# ANALOG_DATA.net
KiCad netlist of a schematic drawn in Altium Designer
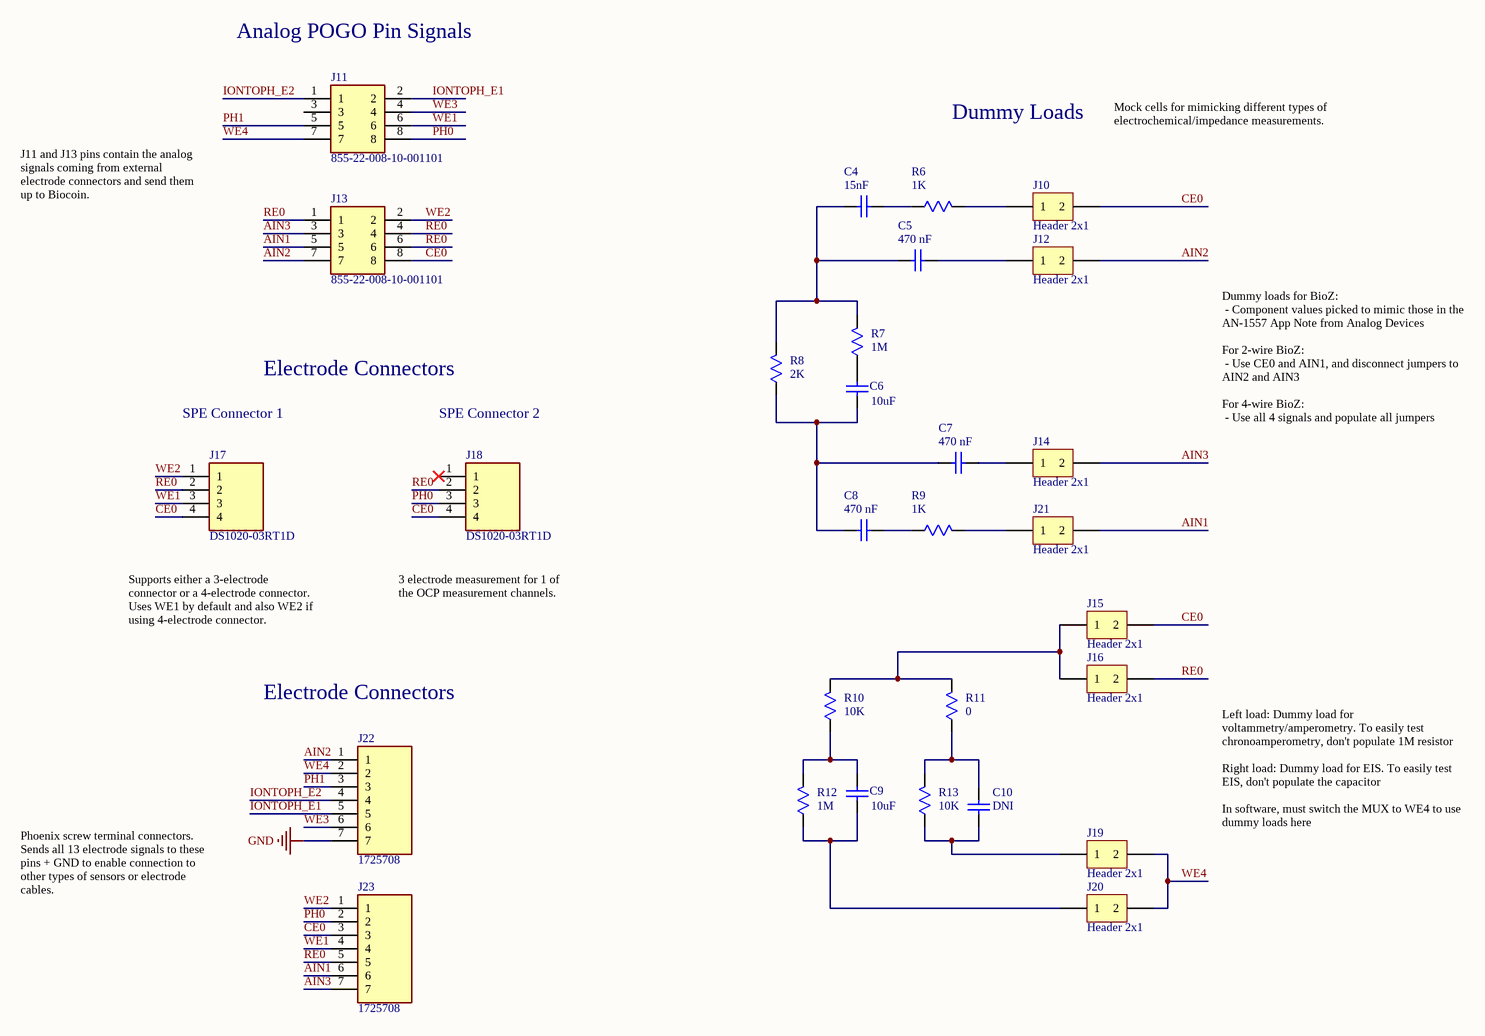
[diagram p0: ANALOG_DATA.SchDoc]

(export (version "E")
  (design (tool "Eeschema 10.0.6"))
  (components
    (comp (ref "C4")
      (value "15nF")
      (footprint "0805-CAP")
      (description "Multilayer Chip Capacitor")
      (fields (field (name "Comment") "CAP") (field (name "DESIGNER") "OMIGA"))
      (libsource (lib "Schlib") (part "CAP SMD"))
    )
    (comp (ref "C5")
      (value "470 nF")
      (footprint "0805-CAP")
      (description "Multilayer Chip Capacitor")
      (fields (field (name "Comment") "CAP") (field (name "DESIGNER") "OMIGA"))
      (libsource (lib "Schlib") (part "CAP SMD"))
    )
    (comp (ref "C6")
      (value "10uF")
      (footprint "0805-CAP")
      (description "Multilayer Chip Capacitor")
      (fields (field (name "Comment") "CAP") (field (name "DESIGNER") "OMIGA"))
      (libsource (lib "Schlib") (part "CAP SMD"))
    )
    (comp (ref "C7")
      (value "470 nF")
      (footprint "0805-CAP")
      (description "Multilayer Chip Capacitor")
      (fields (field (name "Comment") "CAP") (field (name "DESIGNER") "OMIGA"))
      (libsource (lib "Schlib") (part "CAP SMD"))
    )
    (comp (ref "C8")
      (value "470 nF")
      (footprint "0805-CAP")
      (description "Multilayer Chip Capacitor")
      (fields (field (name "Comment") "CAP") (field (name "DESIGNER") "OMIGA"))
      (libsource (lib "Schlib") (part "CAP SMD"))
    )
    (comp (ref "C9")
      (value "10uF")
      (footprint "0805-CAP")
      (description "Multilayer Chip Capacitor")
      (fields (field (name "Comment") "CAP") (field (name "DESIGNER") "OMIGA"))
      (libsource (lib "Schlib") (part "CAP SMD"))
    )
    (comp (ref "C10")
      (value "DNI")
      (footprint "0805-CAP")
      (description "Multilayer Chip Capacitor")
      (fields (field (name "Comment") "CAP") (field (name "DESIGNER") "OMIGA"))
      (libsource (lib "Schlib") (part "CAP SMD"))
    )
    (comp (ref "J10")
      (value "Header 2x1")
      (footprint "Header 1x2")
      (description "Pin Header 2x1")
      (fields (field (name "DESIGNER") "OMIGA"))
      (libsource (lib "Schlib") (part "Header 2x1"))
    )
    (comp (ref "J11")
      (value "855-22-008-10-001101")
      (footprint "8552200810001101")
      (libsource (lib "Schlib") (part "8 pin Pogo Pin Male Header"))
    )
    (comp (ref "J12")
      (value "Header 2x1")
      (footprint "Header 1x2")
      (description "Pin Header 2x1")
      (fields (field (name "DESIGNER") "OMIGA"))
      (libsource (lib "Schlib") (part "Header 2x1"))
    )
    (comp (ref "J13")
      (value "855-22-008-10-001101")
      (footprint "8552200810001101")
      (libsource (lib "Schlib") (part "8 pin Pogo Pin Male Header"))
    )
    (comp (ref "J14")
      (value "Header 2x1")
      (footprint "Header 1x2")
      (description "Pin Header 2x1")
      (fields (field (name "DESIGNER") "OMIGA"))
      (libsource (lib "Schlib") (part "Header 2x1"))
    )
    (comp (ref "J15")
      (value "Header 2x1")
      (footprint "Header 1x2")
      (description "Pin Header 2x1")
      (fields (field (name "DESIGNER") "OMIGA"))
      (libsource (lib "Schlib") (part "Header 2x1"))
    )
    (comp (ref "J16")
      (value "Header 2x1")
      (footprint "Header 1x2")
      (description "Pin Header 2x1")
      (fields (field (name "DESIGNER") "OMIGA"))
      (libsource (lib "Schlib") (part "Header 2x1"))
    )
    (comp (ref "J17")
      (value "DS1020-03RT1D")
      (footprint "55203144-2")
      (description "3 pin right angle SPE connector. Can also use the 5-520315-3-ND")
      (libsource (lib "Schlib") (part "SPE Connector 3 pin"))
    )
    (comp (ref "J18")
      (value "DS1020-03RT1D")
      (footprint "55203144-2")
      (description "3 pin right angle SPE connector. Can also use the 5-520315-3-ND")
      (libsource (lib "Schlib") (part "SPE Connector 3 pin"))
    )
    (comp (ref "J19")
      (value "Header 2x1")
      (footprint "Header 1x2")
      (description "Pin Header 2x1")
      (fields (field (name "DESIGNER") "OMIGA"))
      (libsource (lib "Schlib") (part "Header 2x1"))
    )
    (comp (ref "J20")
      (value "Header 2x1")
      (footprint "Header 1x2")
      (description "Pin Header 2x1")
      (fields (field (name "DESIGNER") "OMIGA"))
      (libsource (lib "Schlib") (part "Header 2x1"))
    )
    (comp (ref "J21")
      (value "Header 2x1")
      (footprint "Header 1x2")
      (description "Pin Header 2x1")
      (fields (field (name "DESIGNER") "OMIGA"))
      (libsource (lib "Schlib") (part "Header 2x1"))
    )
    (comp (ref "J22")
      (value "1725708")
      (footprint "1725708")
      (description "Connector")
      (libsource (lib "Schlib") (part "1725708"))
    )
    (comp (ref "J23")
      (value "1725708")
      (footprint "1725708")
      (description "Connector")
      (libsource (lib "Schlib") (part "1725708"))
    )
    (comp (ref "R6")
      (value "1K")
      (footprint "0805-RES")
      (description "Surface Mount Resistor")
      (fields (field (name "Comment") "RES") (field (name "DESIGNER") "OMIGA"))
      (libsource (lib "Schlib") (part "RES SMD"))
    )
    (comp (ref "R7")
      (value "1M")
      (footprint "0805-RES")
      (description "Surface Mount Resistor")
      (fields (field (name "Comment") "RES") (field (name "DESIGNER") "OMIGA"))
      (libsource (lib "Schlib") (part "RES SMD"))
    )
    (comp (ref "R8")
      (value "2K")
      (footprint "0805-RES")
      (description "Surface Mount Resistor")
      (fields (field (name "Comment") "RES") (field (name "DESIGNER") "OMIGA"))
      (libsource (lib "Schlib") (part "RES SMD"))
    )
    (comp (ref "R9")
      (value "1K")
      (footprint "0805-RES")
      (description "Surface Mount Resistor")
      (fields (field (name "Comment") "RES") (field (name "DESIGNER") "OMIGA"))
      (libsource (lib "Schlib") (part "RES SMD"))
    )
    (comp (ref "R10")
      (value "10K")
      (footprint "0805-RES")
      (description "Surface Mount Resistor")
      (fields (field (name "Comment") "RES") (field (name "DESIGNER") "OMIGA"))
      (libsource (lib "Schlib") (part "RES SMD"))
    )
    (comp (ref "R11")
      (value "0")
      (footprint "0805-RES")
      (description "Surface Mount Resistor")
      (fields (field (name "Comment") "RES") (field (name "DESIGNER") "OMIGA"))
      (libsource (lib "Schlib") (part "RES SMD"))
    )
    (comp (ref "R12")
      (value "1M")
      (footprint "0805-RES")
      (description "Surface Mount Resistor")
      (fields (field (name "Comment") "RES") (field (name "DESIGNER") "OMIGA"))
      (libsource (lib "Schlib") (part "RES SMD"))
    )
    (comp (ref "R13")
      (value "10K")
      (footprint "0805-RES")
      (description "Surface Mount Resistor")
      (fields (field (name "Comment") "RES") (field (name "DESIGNER") "OMIGA"))
      (libsource (lib "Schlib") (part "RES SMD"))
    )
  )
  (nets
    (net (code "1") (name "/AIN1") (class "Default")
      (node (ref "J13") (pin "5") (pinfunction "5_5") (pintype "passive"))
      (node (ref "J21") (pin "2") (pinfunction "2_2") (pintype "passive"))
      (node (ref "J23") (pin "6") (pinfunction "6_6") (pintype "passive"))
    )
    (net (code "2") (name "/AIN2") (class "Default")
      (node (ref "J12") (pin "2") (pinfunction "2_2") (pintype "passive"))
      (node (ref "J13") (pin "7") (pinfunction "7_7") (pintype "passive"))
      (node (ref "J22") (pin "1") (pinfunction "1_1") (pintype "passive"))
    )
    (net (code "3") (name "/AIN3") (class "Default")
      (node (ref "J13") (pin "3") (pinfunction "3_3") (pintype "passive"))
      (node (ref "J14") (pin "2") (pinfunction "2_2") (pintype "passive"))
      (node (ref "J23") (pin "7") (pinfunction "7_7") (pintype "passive"))
    )
    (net (code "4") (name "/CE0") (class "Default")
      (node (ref "J10") (pin "2") (pinfunction "2_2") (pintype "passive"))
      (node (ref "J13") (pin "8") (pinfunction "8_8") (pintype "passive"))
      (node (ref "J15") (pin "2") (pinfunction "2_2") (pintype "passive"))
      (node (ref "J17") (pin "4") (pinfunction "4_4") (pintype "passive"))
      (node (ref "J18") (pin "4") (pinfunction "4_4") (pintype "passive"))
      (node (ref "J23") (pin "3") (pinfunction "3_3") (pintype "passive"))
    )
    (net (code "5") (name "/IONTOPH_E1") (class "Default")
      (node (ref "J11") (pin "2") (pinfunction "2_2") (pintype "passive"))
      (node (ref "J22") (pin "5") (pinfunction "5_5") (pintype "passive"))
    )
    (net (code "6") (name "/IONTOPH_E2") (class "Default")
      (node (ref "J11") (pin "1") (pinfunction "1_1") (pintype "passive"))
      (node (ref "J22") (pin "4") (pinfunction "4_4") (pintype "passive"))
    )
    (net (code "7") (name "/PH0") (class "Default")
      (node (ref "J11") (pin "8") (pinfunction "8_8") (pintype "passive"))
      (node (ref "J18") (pin "3") (pinfunction "3_3") (pintype "passive"))
      (node (ref "J23") (pin "2") (pinfunction "2_2") (pintype "passive"))
    )
    (net (code "8") (name "/PH1") (class "Default")
      (node (ref "J11") (pin "5") (pinfunction "5_5") (pintype "passive"))
      (node (ref "J22") (pin "3") (pinfunction "3_3") (pintype "passive"))
    )
    (net (code "9") (name "/RE0") (class "Default")
      (node (ref "J13") (pin "1") (pinfunction "1_1") (pintype "passive"))
      (node (ref "J13") (pin "4") (pinfunction "4_4") (pintype "passive"))
      (node (ref "J13") (pin "6") (pinfunction "6_6") (pintype "passive"))
      (node (ref "J16") (pin "2") (pinfunction "2_2") (pintype "passive"))
      (node (ref "J17") (pin "2") (pinfunction "2_2") (pintype "passive"))
      (node (ref "J18") (pin "2") (pinfunction "2_2") (pintype "passive"))
      (node (ref "J23") (pin "5") (pinfunction "5_5") (pintype "passive"))
    )
    (net (code "10") (name "/WE1") (class "Default")
      (node (ref "J11") (pin "6") (pinfunction "6_6") (pintype "passive"))
      (node (ref "J17") (pin "3") (pinfunction "3_3") (pintype "passive"))
      (node (ref "J23") (pin "4") (pinfunction "4_4") (pintype "passive"))
    )
    (net (code "11") (name "/WE2") (class "Default")
      (node (ref "J13") (pin "2") (pinfunction "2_2") (pintype "passive"))
      (node (ref "J17") (pin "1") (pinfunction "1_1") (pintype "passive"))
      (node (ref "J23") (pin "1") (pinfunction "1_1") (pintype "passive"))
    )
    (net (code "12") (name "/WE3") (class "Default")
      (node (ref "J11") (pin "4") (pinfunction "4_4") (pintype "passive"))
      (node (ref "J22") (pin "6") (pinfunction "6_6") (pintype "passive"))
    )
    (net (code "13") (name "/WE4") (class "Default")
      (node (ref "J11") (pin "7") (pinfunction "7_7") (pintype "passive"))
      (node (ref "J19") (pin "2") (pinfunction "2_2") (pintype "passive"))
      (node (ref "J20") (pin "2") (pinfunction "2_2") (pintype "passive"))
      (node (ref "J22") (pin "2") (pinfunction "2_2") (pintype "passive"))
    )
    (net (code "14") (name "GND") (class "Default")
      (node (ref "J22") (pin "7") (pinfunction "7_7") (pintype "passive"))
    )
    (net (code "15") (name "Net-(C4-Pad1)") (class "Default")
      (node (ref "C4") (pin "1") (pinfunction "1_1") (pintype "passive"))
      (node (ref "C5") (pin "1") (pinfunction "1_1") (pintype "passive"))
      (node (ref "R7") (pin "2") (pinfunction "2_2") (pintype "passive"))
      (node (ref "R8") (pin "2") (pinfunction "2_2") (pintype "passive"))
    )
    (net (code "16") (name "Net-(C4-Pad2)") (class "Default")
      (node (ref "C4") (pin "2") (pinfunction "2_2") (pintype "passive"))
      (node (ref "R6") (pin "1") (pinfunction "1_1") (pintype "passive"))
    )
    (net (code "17") (name "Net-(C5-Pad2)") (class "Default")
      (node (ref "C5") (pin "2") (pinfunction "2_2") (pintype "passive"))
      (node (ref "J12") (pin "1") (pinfunction "1_1") (pintype "passive"))
    )
    (net (code "18") (name "Net-(C6-Pad1)") (class "Default")
      (node (ref "C6") (pin "1") (pinfunction "1_1") (pintype "passive"))
      (node (ref "C7") (pin "1") (pinfunction "1_1") (pintype "passive"))
      (node (ref "C8") (pin "1") (pinfunction "1_1") (pintype "passive"))
      (node (ref "R8") (pin "1") (pinfunction "1_1") (pintype "passive"))
    )
    (net (code "19") (name "Net-(C6-Pad2)") (class "Default")
      (node (ref "C6") (pin "2") (pinfunction "2_2") (pintype "passive"))
      (node (ref "R7") (pin "1") (pinfunction "1_1") (pintype "passive"))
    )
    (net (code "20") (name "Net-(C7-Pad2)") (class "Default")
      (node (ref "C7") (pin "2") (pinfunction "2_2") (pintype "passive"))
      (node (ref "J14") (pin "1") (pinfunction "1_1") (pintype "passive"))
    )
    (net (code "21") (name "Net-(C8-Pad2)") (class "Default")
      (node (ref "C8") (pin "2") (pinfunction "2_2") (pintype "passive"))
      (node (ref "R9") (pin "1") (pinfunction "1_1") (pintype "passive"))
    )
    (net (code "22") (name "Net-(C9-Pad1)") (class "Default")
      (node (ref "C9") (pin "1") (pinfunction "1_1") (pintype "passive"))
      (node (ref "J20") (pin "1") (pinfunction "1_1") (pintype "passive"))
      (node (ref "R12") (pin "1") (pinfunction "1_1") (pintype "passive"))
    )
    (net (code "23") (name "Net-(C9-Pad2)") (class "Default")
      (node (ref "C9") (pin "2") (pinfunction "2_2") (pintype "passive"))
      (node (ref "R10") (pin "1") (pinfunction "1_1") (pintype "passive"))
      (node (ref "R12") (pin "2") (pinfunction "2_2") (pintype "passive"))
    )
    (net (code "24") (name "Net-(C10-Pad1)") (class "Default")
      (node (ref "C10") (pin "1") (pinfunction "1_1") (pintype "passive"))
      (node (ref "J19") (pin "1") (pinfunction "1_1") (pintype "passive"))
      (node (ref "R13") (pin "1") (pinfunction "1_1") (pintype "passive"))
    )
    (net (code "25") (name "Net-(C10-Pad2)") (class "Default")
      (node (ref "C10") (pin "2") (pinfunction "2_2") (pintype "passive"))
      (node (ref "R11") (pin "1") (pinfunction "1_1") (pintype "passive"))
      (node (ref "R13") (pin "2") (pinfunction "2_2") (pintype "passive"))
    )
    (net (code "26") (name "Net-(J10-Pad1)") (class "Default")
      (node (ref "J10") (pin "1") (pinfunction "1_1") (pintype "passive"))
      (node (ref "R6") (pin "2") (pinfunction "2_2") (pintype "passive"))
    )
    (net (code "27") (name "Net-(J15-Pad1)") (class "Default")
      (node (ref "J15") (pin "1") (pinfunction "1_1") (pintype "passive"))
      (node (ref "J16") (pin "1") (pinfunction "1_1") (pintype "passive"))
      (node (ref "R10") (pin "2") (pinfunction "2_2") (pintype "passive"))
      (node (ref "R11") (pin "2") (pinfunction "2_2") (pintype "passive"))
    )
    (net (code "28") (name "Net-(J21-Pad1)") (class "Default")
      (node (ref "J21") (pin "1") (pinfunction "1_1") (pintype "passive"))
      (node (ref "R9") (pin "2") (pinfunction "2_2") (pintype "passive"))
    )
    (net (code "29") (name "unconnected-(J11-Pad3)") (class "Default")
      (node (ref "J11") (pin "3") (pinfunction "3_3") (pintype "passive"))
    )
    (net (code "30") (name "unconnected-(J18-Pad1)") (class "Default")
      (node (ref "J18") (pin "1") (pinfunction "1_1") (pintype "passive+no_connect"))
    )
  )
)
